# 200_UART_TO_USB.net
KiCad netlist of a schematic drawn in Altium Designer
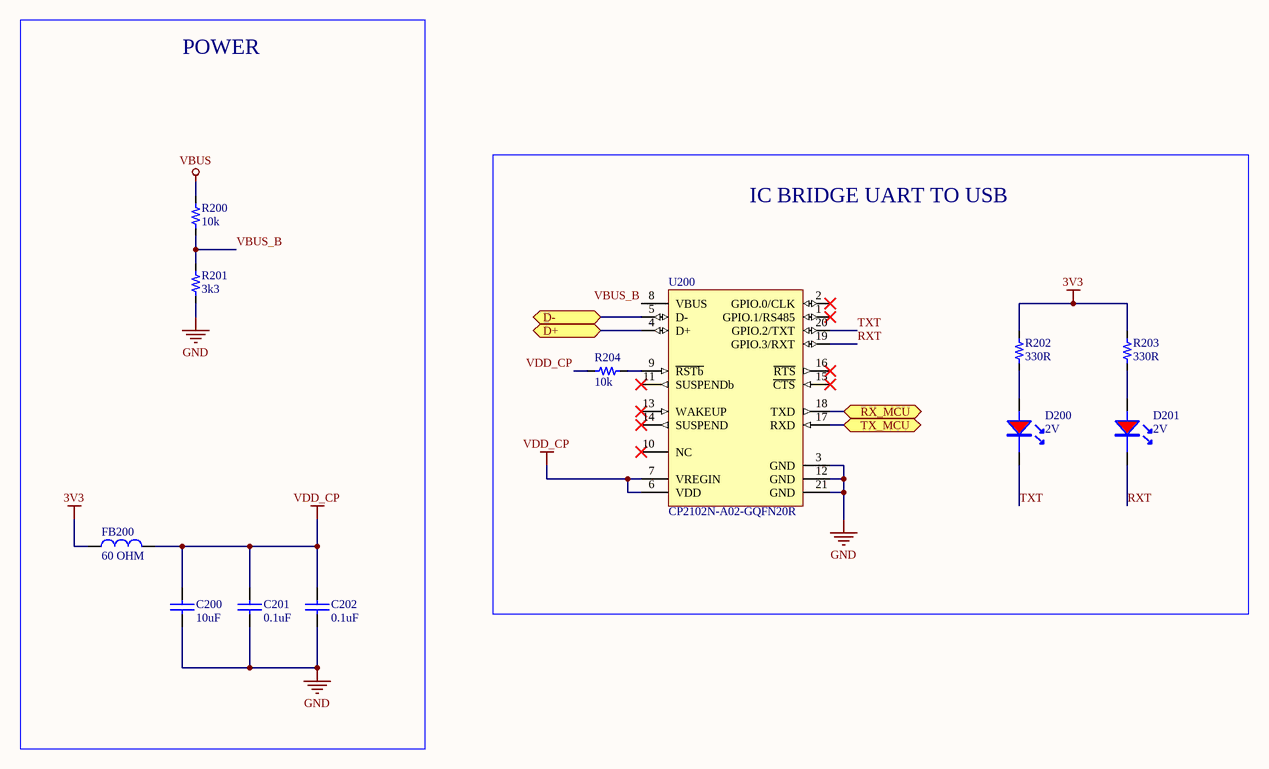
[diagram p0: 200_UART_TO_USB.SchDoc]

(export (version "E")
  (design (tool "Eeschema 10.0.6"))
  (components
    (comp (ref "C200")
      (value "10uF")
      (footprint "0603_cap")
      (description "10V 10uF X5R ±10% 0603 Multilayer Ceramic Capacitors MLCC - SMD/SMT ROHS")
      (fields
        (field (name "MANUFACTURER") "CCTC")
        (field (name "MANUFACTURER PART NUMBER") "TCC0603X5R106K100CT")
      )
      (libsource (lib "shared_lib") (part "Cap_10uF_0603_10V"))
    )
    (comp (ref "C201")
      (value "0.1uF")
      (footprint "0603_cap")
      (description "50V 100nF Y5V -20%~+80% 0603 Multilayer Ceramic Capacitors MLCC - SMD/SMT ROHS")
      (fields
        (field (name "MANUFACTURER") "Walsin Tech Corp")
        (field (name "MANUFACTURER PART NUMBER") "0603F104Z500CT")
      )
      (libsource (lib "shared_lib") (part "Cap_0.1uF_0603_50V"))
    )
    (comp (ref "C202")
      (value "0.1uF")
      (footprint "0603_cap")
      (description "50V 100nF Y5V -20%~+80% 0603 Multilayer Ceramic Capacitors MLCC - SMD/SMT ROHS")
      (fields
        (field (name "MANUFACTURER") "Walsin Tech Corp")
        (field (name "MANUFACTURER PART NUMBER") "0603F104Z500CT")
      )
      (libsource (lib "shared_lib") (part "Cap_0.1uF_0603_50V"))
    )
    (comp (ref "D200")
      (value "2V")
      (footprint "0805_LED")
      (description "LED RED CLEAR 0805 SMD")
      (fields
        (field (name "MANUFACTURER") "XINGLIGHT")
        (field (name "MANUFACTURER PART NUMBER") "XL-2012SURC")
      )
      (libsource (lib "shared_lib") (part "LED_0805_RED"))
    )
    (comp (ref "D201")
      (value "2V")
      (footprint "0805_LED")
      (description "LED RED CLEAR 0805 SMD")
      (fields
        (field (name "MANUFACTURER") "XINGLIGHT")
        (field (name "MANUFACTURER PART NUMBER") "XL-2012SURC")
      )
      (libsource (lib "shared_lib") (part "LED_0805_RED"))
    )
    (comp (ref "FB200")
      (value "60 OHM")
      (footprint "0603_fb")
      (description "2A 1 100mΩ 60Ω@100MHz ±25% 0603 Ferrite Beads ROHS")
      (fields
        (field (name "MANUFACTURER") "TAI-TECH")
        (field (name "MANUFACTURER PART NUMBER") "HCB1608KF-600T20")
      )
      (libsource (lib "shared_lib") (part "FB_60_0603_2A"))
    )
    (comp (ref "R200")
      (value "10k")
      (footprint "0603_res")
      (description "RES SMD 10k OHM 5% 1/10W 0603")
      (fields (field (name "MANUFACTURER") "FOJAN") (field (name "MANUFACTURER PART NUMBER") "FRC0603J103TS"))
      (libsource (lib "shared_lib") (part "Res_10k_0603_1/10W"))
    )
    (comp (ref "R201")
      (value "3k3")
      (footprint "0603_res")
      (description "RES SMD 3k3 OHM 5% 1/10W 0603")
      (fields
        (field (name "MANUFACTURER") "FOJAN")
        (field (name "MANUFACTURER PART NUMBER") "FRC0603J332 TS")
      )
      (libsource (lib "shared_lib") (part "Res_3k3_0603_1/10W"))
    )
    (comp (ref "R202")
      (value "330R")
      (footprint "0603_res")
      (description "RES SMD 330R OHM 5% 1/10W 0603")
      (fields
        (field (name "MANUFACTURER") "FOJAN")
        (field (name "MANUFACTURER PART NUMBER") "FRC0603J331 TS")
      )
      (libsource (lib "shared_lib") (part "Res_330R_0603_1/10W"))
    )
    (comp (ref "R203")
      (value "330R")
      (footprint "0603_res")
      (description "RES SMD 330R OHM 5% 1/10W 0603")
      (fields
        (field (name "MANUFACTURER") "FOJAN")
        (field (name "MANUFACTURER PART NUMBER") "FRC0603J331 TS")
      )
      (libsource (lib "shared_lib") (part "Res_330R_0603_1/10W"))
    )
    (comp (ref "R204")
      (value "10k")
      (footprint "0603_res")
      (description "RES SMD 10k OHM 5% 1/10W 0603")
      (fields (field (name "MANUFACTURER") "FOJAN") (field (name "MANUFACTURER PART NUMBER") "FRC0603J103TS"))
      (libsource (lib "shared_lib") (part "Res_10k_0603_1/10W"))
    )
    (comp (ref "U200")
      (value "CP2102N-A02-GQFN20R")
      (footprint "WFQFN_20_EP_3X3MM")
      (description "IC USB TO UART BRIDGE QFN20")
      (fields (field (name "MANUFACTURER") "Silicon Labs"))
      (libsource (lib "shared_lib") (part "IC_SGL_USB2UART-BRIDGE_20QFN"))
    )
  )
  (nets
    (net (code "1") (name "/D+") (class "Default")
      (node (ref "U200") (pin "4") (pinfunction "D+_4") (pintype "bidirectional"))
    )
    (net (code "2") (name "/D-") (class "Default")
      (node (ref "U200") (pin "5") (pinfunction "D-_5") (pintype "bidirectional"))
    )
    (net (code "3") (name "/RXT") (class "Default")
      (node (ref "D201") (pin "2") (pinfunction "2_2") (pintype "passive"))
      (node (ref "U200") (pin "19") (pinfunction "GPIO.3/RXT_19") (pintype "bidirectional"))
    )
    (net (code "4") (name "/RX_MCU") (class "Default")
      (node (ref "U200") (pin "18") (pinfunction "TXD_18") (pintype "output"))
    )
    (net (code "5") (name "/TXT") (class "Default")
      (node (ref "D200") (pin "2") (pinfunction "2_2") (pintype "passive"))
      (node (ref "U200") (pin "20") (pinfunction "GPIO.2/TXT_20") (pintype "bidirectional"))
    )
    (net (code "6") (name "/TX_MCU") (class "Default")
      (node (ref "U200") (pin "17") (pinfunction "RXD_17") (pintype "input"))
    )
    (net (code "7") (name "/VBUS_B") (class "Default")
      (node (ref "R200") (pin "1") (pinfunction "1_1") (pintype "passive"))
      (node (ref "R201") (pin "2") (pinfunction "2_2") (pintype "passive"))
      (node (ref "U200") (pin "8") (pinfunction "VBUS_8") (pintype "power_in"))
    )
    (net (code "8") (name "3V3") (class "Default")
      (node (ref "FB200") (pin "1") (pinfunction "1_1") (pintype "passive"))
      (node (ref "R202") (pin "2") (pinfunction "2_2") (pintype "passive"))
      (node (ref "R203") (pin "2") (pinfunction "2_2") (pintype "passive"))
    )
    (net (code "9") (name "GND") (class "Default")
      (node (ref "C200") (pin "2") (pinfunction "2_2") (pintype "passive"))
      (node (ref "C201") (pin "2") (pinfunction "2_2") (pintype "passive"))
      (node (ref "C202") (pin "2") (pinfunction "2_2") (pintype "passive"))
      (node (ref "R201") (pin "1") (pinfunction "1_1") (pintype "passive"))
      (node (ref "U200") (pin "12") (pinfunction "GND_12") (pintype "power_in"))
      (node (ref "U200") (pin "21") (pinfunction "GND_21") (pintype "power_in"))
      (node (ref "U200") (pin "3") (pinfunction "GND_3") (pintype "power_in"))
    )
    (net (code "10") (name "Net-(D200-A)") (class "Default")
      (node (ref "D200") (pin "1") (pinfunction "A_1") (pintype "passive"))
      (node (ref "R202") (pin "1") (pinfunction "1_1") (pintype "passive"))
    )
    (net (code "11") (name "Net-(D201-A)") (class "Default")
      (node (ref "D201") (pin "1") (pinfunction "A_1") (pintype "passive"))
      (node (ref "R203") (pin "1") (pinfunction "1_1") (pintype "passive"))
    )
    (net (code "12") (name "Net-(U200-~{RSTb})") (class "Default")
      (node (ref "R204") (pin "2") (pinfunction "2_2") (pintype "passive"))
      (node (ref "U200") (pin "9") (pinfunction "~{RSTb}_9") (pintype "input"))
    )
    (net (code "13") (name "VBUS") (class "Default")
      (node (ref "R200") (pin "2") (pinfunction "2_2") (pintype "passive"))
    )
    (net (code "14") (name "VDD_CP") (class "Default")
      (node (ref "C200") (pin "1") (pinfunction "1_1") (pintype "passive"))
      (node (ref "C201") (pin "1") (pinfunction "1_1") (pintype "passive"))
      (node (ref "C202") (pin "1") (pinfunction "1_1") (pintype "passive"))
      (node (ref "FB200") (pin "2") (pinfunction "2_2") (pintype "passive"))
      (node (ref "R204") (pin "1") (pinfunction "1_1") (pintype "passive"))
      (node (ref "U200") (pin "6") (pinfunction "VDD_6") (pintype "power_in"))
      (node (ref "U200") (pin "7") (pinfunction "VREGIN_7") (pintype "power_in"))
    )
    (net (code "15") (name "unconnected-(U200-GPIO.0{slash}CLK-Pad2)") (class "Default")
      (node (ref "U200") (pin "2") (pinfunction "GPIO.0/CLK_2") (pintype "bidirectional+no_connect"))
    )
    (net (code "16") (name "unconnected-(U200-GPIO.1{slash}RS485-Pad1)") (class "Default")
      (node (ref "U200") (pin "1") (pinfunction "GPIO.1/RS485_1") (pintype "bidirectional+no_connect"))
    )
    (net (code "17") (name "unconnected-(U200-NC-Pad10)") (class "Default")
      (node (ref "U200") (pin "10") (pinfunction "NC_10") (pintype "passive+no_connect"))
    )
    (net (code "18") (name "unconnected-(U200-SUSPEND-Pad14)") (class "Default")
      (node (ref "U200") (pin "14") (pinfunction "SUSPEND_14") (pintype "output+no_connect"))
    )
    (net (code "19") (name "unconnected-(U200-SUSPENDb-Pad11)") (class "Default")
      (node (ref "U200") (pin "11") (pinfunction "SUSPENDb_11") (pintype "output+no_connect"))
    )
    (net (code "20") (name "unconnected-(U200-WAKEUP-Pad13)") (class "Default")
      (node (ref "U200") (pin "13") (pinfunction "WAKEUP_13") (pintype "input+no_connect"))
    )
    (net (code "21") (name "unconnected-(U200-~{CTS}-Pad15)") (class "Default")
      (node (ref "U200") (pin "15") (pinfunction "~{CTS}_15") (pintype "input+no_connect"))
    )
    (net (code "22") (name "unconnected-(U200-~{RTS}-Pad16)") (class "Default")
      (node (ref "U200") (pin "16") (pinfunction "~{RTS}_16") (pintype "output+no_connect"))
    )
  )
)
